# J1850_Tacho.net
KiCad netlist of a schematic drawn in Altium Designer
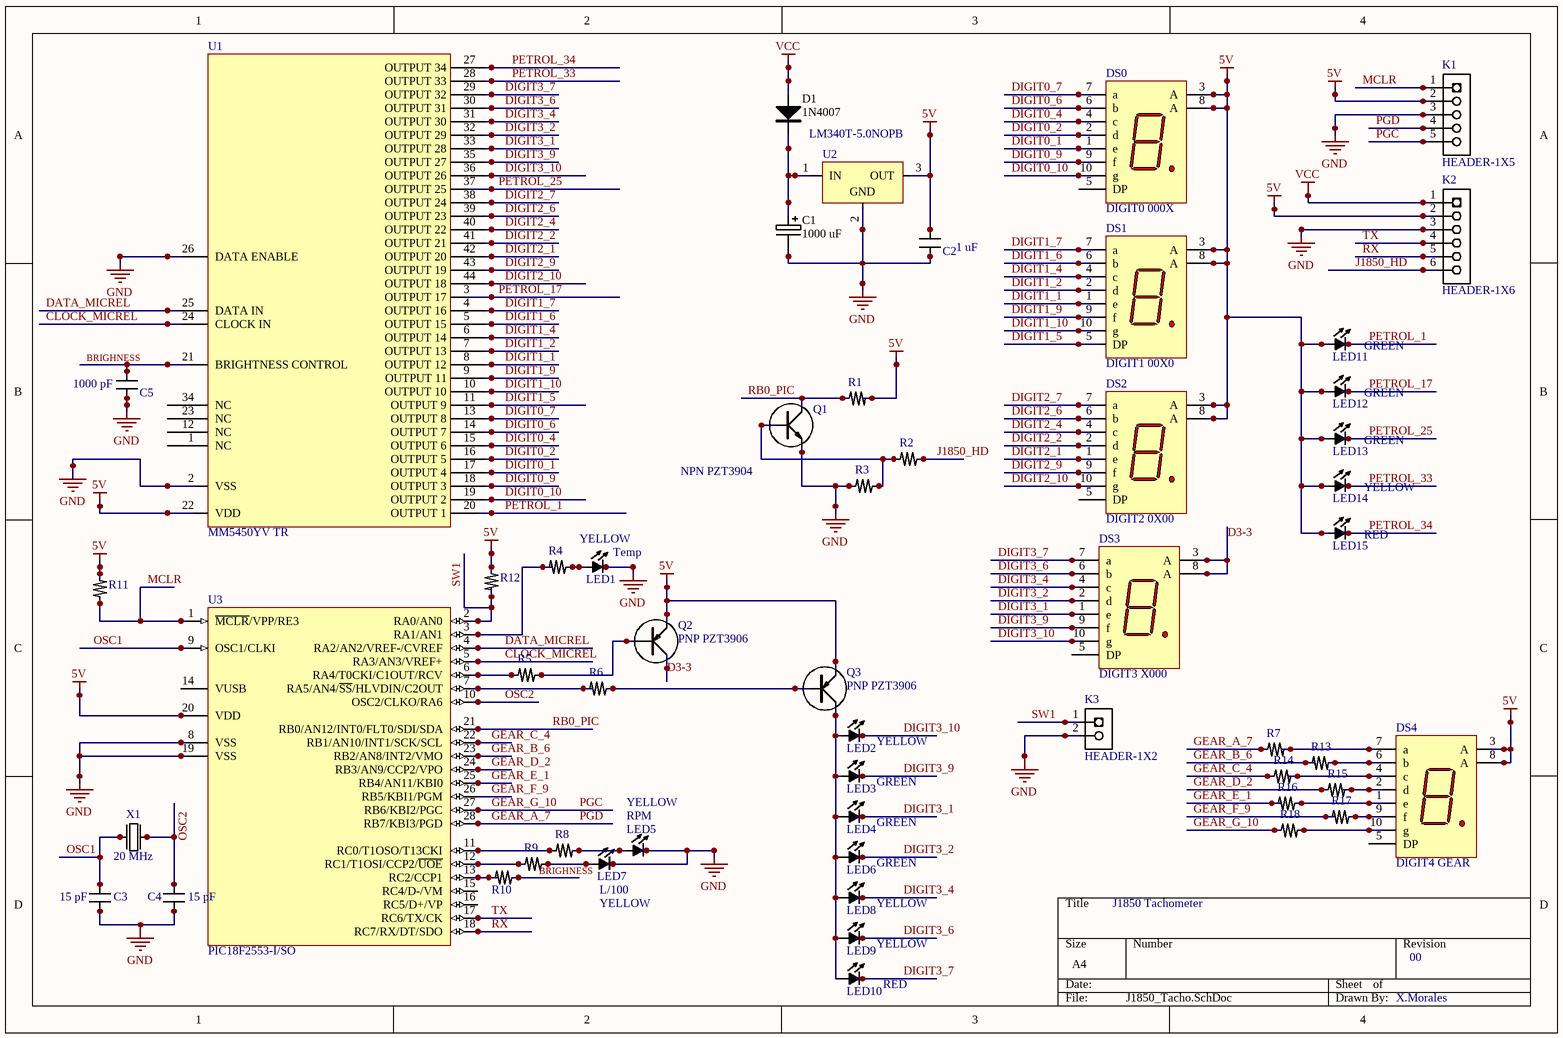
[diagram p0: J1850_Tacho.SchDoc]

(export (version "E")
  (design (tool "Eeschema 10.0.6"))
  (components
    (comp (ref "C1")
      (value "1000 uF")
      (footprint "AXIAL CAP")
      (description "AXIAL CAPACITOR")
      (libsource (lib "J1850_tacho") (part "AXIAL CAP"))
    )
    (comp (ref "C2")
      (value "1 uF")
      (footprint "C_0805")
      (description "Capacitor SMD 0805")
      (fields (field (name "PUBLISHER") "Altium Limited"))
      (libsource (lib "J1850_tacho") (part "Capacitor SMD 0805"))
    )
    (comp (ref "C3")
      (value "15 pF")
      (footprint "C_0805")
      (description "Capacitor SMD 0805")
      (fields (field (name "PUBLISHER") "Altium Limited"))
      (libsource (lib "J1850_tacho") (part "Capacitor SMD 0805"))
    )
    (comp (ref "C4")
      (value "15 pF")
      (footprint "C_0805")
      (description "Capacitor SMD 0805")
      (fields (field (name "PUBLISHER") "Altium Limited"))
      (libsource (lib "J1850_tacho") (part "Capacitor SMD 0805"))
    )
    (comp (ref "C5")
      (value "1000 pF")
      (footprint "C_0805")
      (description "Capacitor SMD 0805")
      (fields (field (name "PUBLISHER") "Altium Limited"))
      (libsource (lib "J1850_tacho") (part "Capacitor SMD 0805"))
    )
    (comp (ref "D1")
      (value "1N4007")
      (footprint "1N400X")
      (description "1N4001")
      (libsource (lib "J1850_tacho") (part "1N4001"))
    )
    (comp (ref "DS0")
      (value "SA56-51ZGWA")
      (footprint "H-10")
      (description "14.22 mm Low Current HER 7-Segment Display: CA, RH DP")
      (libsource (lib "J1850_tacho") (part "7Segment"))
    )
    (comp (ref "DS1")
      (value "SA56-51ZGWA")
      (footprint "H-10")
      (description "14.22 mm Low Current HER 7-Segment Display: CA, RH DP")
      (fields (field (name "PUBLISHER") "Altium Limited"))
      (libsource (lib "J1850_tacho") (part "HDSP-5551"))
    )
    (comp (ref "DS2")
      (value "SA56-51ZGWA")
      (footprint "H-10")
      (description "14.22 mm Low Current HER 7-Segment Display: CA, RH DP")
      (fields (field (name "PUBLISHER") "Altium Limited"))
      (libsource (lib "J1850_tacho") (part "HDSP-5551"))
    )
    (comp (ref "DS3")
      (value "SA56-51ZGWA")
      (footprint "H-10")
      (description "14.22 mm Low Current HER 7-Segment Display: CA, RH DP")
      (fields (field (name "PUBLISHER") "Altium Limited"))
      (libsource (lib "J1850_tacho") (part "HDSP-5551"))
    )
    (comp (ref "DS4")
      (value "SA56-51ZGWA")
      (footprint "H-10")
      (description "14.22 mm Low Current HER 7-Segment Display: CA, RH DP")
      (fields (field (name "PUBLISHER") "Altium Limited"))
      (libsource (lib "J1850_tacho") (part "HDSP-5551"))
    )
    (comp (ref "K1")
      (value "HEADER-1X5")
      (footprint "HEADER-1X5")
      (description "PINHEADER 1X5")
      (libsource (lib "J1850_tacho") (part "HEADER-1X5"))
    )
    (comp (ref "K2")
      (value "HEADER-1X6")
      (footprint "HEADER-1X6")
      (libsource (lib "J1850_tacho") (part "HEADER-1X6"))
    )
    (comp (ref "K3")
      (value "HEADER-1X2")
      (footprint "HEADER-1X2")
      (libsource (lib "J1850_tacho") (part "HEADER-1X2"))
    )
    (comp (ref "LED1")
      (value "YELLOW")
      (footprint "LED_0805")
      (description "LED SMD 0805")
      (libsource (lib "J1850_tacho") (part "LED SMD 0805"))
    )
    (comp (ref "LED2")
      (value "YELLOW")
      (footprint "LED_0805")
      (description "LED SMD 0805")
      (libsource (lib "J1850_tacho") (part "LED SMD 0805"))
    )
    (comp (ref "LED3")
      (value "GREEN")
      (footprint "LED_0805")
      (description "LED SMD 0805")
      (libsource (lib "J1850_tacho") (part "LED SMD 0805"))
    )
    (comp (ref "LED4")
      (value "GREEN")
      (footprint "LED_0805")
      (description "LED SMD 0805")
      (libsource (lib "J1850_tacho") (part "LED SMD 0805"))
    )
    (comp (ref "LED5")
      (value "YELLOW")
      (footprint "LED_0805")
      (description "LED SMD 0805")
      (libsource (lib "J1850_tacho") (part "LED SMD 0805"))
    )
    (comp (ref "LED6")
      (value "GREEN")
      (footprint "LED_0805")
      (description "LED SMD 0805")
      (libsource (lib "J1850_tacho") (part "LED SMD 0805"))
    )
    (comp (ref "LED7")
      (value "YELLOW")
      (footprint "LED_0805")
      (description "LED SMD 0805")
      (libsource (lib "J1850_tacho") (part "LED SMD 0805"))
    )
    (comp (ref "LED8")
      (value "YELLOW")
      (footprint "LED_0805")
      (description "LED SMD 0805")
      (libsource (lib "J1850_tacho") (part "LED SMD 0805"))
    )
    (comp (ref "LED9")
      (value "YELLOW")
      (footprint "LED_0805")
      (description "LED SMD 0805")
      (libsource (lib "J1850_tacho") (part "LED SMD 0805"))
    )
    (comp (ref "LED10")
      (value "RED")
      (footprint "LED_0805")
      (description "LED SMD 0805")
      (libsource (lib "J1850_tacho") (part "LED SMD 0805"))
    )
    (comp (ref "LED11")
      (value "GREEN")
      (footprint "LED_0805")
      (description "LED SMD 0805")
      (libsource (lib "J1850_tacho") (part "LED SMD 0805"))
    )
    (comp (ref "LED12")
      (value "GREEN")
      (footprint "LED_0805")
      (description "LED SMD 0805")
      (libsource (lib "J1850_tacho") (part "LED SMD 0805"))
    )
    (comp (ref "LED13")
      (value "GREEN")
      (footprint "LED_0805")
      (description "LED SMD 0805")
      (libsource (lib "J1850_tacho") (part "LED SMD 0805"))
    )
    (comp (ref "LED14")
      (value "YELLOW")
      (footprint "LED_0805")
      (description "LED SMD 0805")
      (libsource (lib "J1850_tacho") (part "LED SMD 0805"))
    )
    (comp (ref "LED15")
      (value "RED")
      (footprint "LED_0805")
      (description "LED SMD 0805")
      (libsource (lib "J1850_tacho") (part "LED SMD 0805"))
    )
    (comp (ref "Q1")
      (value "NPN PZT3904")
      (footprint "SOT223")
      (description "NPN TRANSISTOR")
      (libsource (lib "J1850_tacho") (part "NPN TRANSISTOR"))
    )
    (comp (ref "Q2")
      (value "PNP PZT3906")
      (footprint "SOT223")
      (description "PNP TRANSISTOR")
      (libsource (lib "J1850_tacho") (part "PNP TRANSISTOR"))
    )
    (comp (ref "Q3")
      (value "PNP PZT3906")
      (footprint "SOT223")
      (description "PNP TRANSISTOR")
      (libsource (lib "J1850_tacho") (part "PNP TRANSISTOR"))
    )
    (comp (ref "R1")
      (value "47 kOhm")
      (footprint "R_0805")
      (description "Resistor SMD 0805")
      (libsource (lib "J1850_tacho") (part "Resistor SMD 0805"))
    )
    (comp (ref "R2")
      (value "47 kOhm")
      (footprint "R_0805")
      (description "Resistor SMD 0805")
      (libsource (lib "J1850_tacho") (part "Resistor SMD 0805"))
    )
    (comp (ref "R3")
      (value "10 kOhm")
      (footprint "R_0805")
      (description "Resistor SMD 0805")
      (libsource (lib "J1850_tacho") (part "Resistor SMD 0805"))
    )
    (comp (ref "R4")
      (value "220 Ohm")
      (footprint "R_0805")
      (description "Resistor SMD 0805")
      (libsource (lib "J1850_tacho") (part "Resistor SMD 0805"))
    )
    (comp (ref "R5")
      (value "1 kOhm")
      (footprint "R_0805")
      (description "Resistor SMD 0805")
      (libsource (lib "J1850_tacho") (part "Resistor SMD 0805"))
    )
    (comp (ref "R6")
      (value "1 kOhm")
      (footprint "R_0805")
      (description "Resistor SMD 0805")
      (libsource (lib "J1850_tacho") (part "Resistor SMD 0805"))
    )
    (comp (ref "R7")
      (value "220 Ohm")
      (footprint "R_0805")
      (description "Resistor SMD 0805")
      (libsource (lib "J1850_tacho") (part "Resistor SMD 0805"))
    )
    (comp (ref "R8")
      (value "220 Ohm")
      (footprint "R_0805")
      (description "Resistor SMD 0805")
      (libsource (lib "J1850_tacho") (part "Resistor SMD 0805"))
    )
    (comp (ref "R9")
      (value "220 Ohm")
      (footprint "R_0805")
      (description "Resistor SMD 0805")
      (libsource (lib "J1850_tacho") (part "Resistor SMD 0805"))
    )
    (comp (ref "R10")
      (value "1200 Ohm")
      (footprint "R_0805")
      (description "Resistor SMD 0805")
      (libsource (lib "J1850_tacho") (part "Resistor SMD 0805"))
    )
    (comp (ref "R11")
      (value "10 kOhm")
      (footprint "R_0805")
      (description "Resistor SMD 0805")
      (libsource (lib "J1850_tacho") (part "Resistor SMD 0805"))
    )
    (comp (ref "R12")
      (value "10 kOhm")
      (footprint "R_0805")
      (description "Resistor SMD 0805")
      (libsource (lib "J1850_tacho") (part "Resistor SMD 0805"))
    )
    (comp (ref "R13")
      (value "220 Ohm")
      (footprint "R_0805")
      (description "Resistor SMD 0805")
      (libsource (lib "J1850_tacho") (part "Resistor SMD 0805"))
    )
    (comp (ref "R14")
      (value "220 Ohm")
      (footprint "R_0805")
      (description "Resistor SMD 0805")
      (libsource (lib "J1850_tacho") (part "Resistor SMD 0805"))
    )
    (comp (ref "R15")
      (value "220 Ohm")
      (footprint "R_0805")
      (description "Resistor SMD 0805")
      (libsource (lib "J1850_tacho") (part "Resistor SMD 0805"))
    )
    (comp (ref "R16")
      (value "220 Ohm")
      (footprint "R_0805")
      (description "Resistor SMD 0805")
      (libsource (lib "J1850_tacho") (part "Resistor SMD 0805"))
    )
    (comp (ref "R17")
      (value "220 Ohm")
      (footprint "R_0805")
      (description "Resistor SMD 0805")
      (libsource (lib "J1850_tacho") (part "Resistor SMD 0805"))
    )
    (comp (ref "R18")
      (value "220 Ohm")
      (footprint "R_0805")
      (description "Resistor SMD 0805")
      (libsource (lib "J1850_tacho") (part "Resistor SMD 0805"))
    )
    (comp (ref "U1")
      (value "MM5450YV TR")
      (footprint "PLCC-L44_M")
      (description "IC DRIVER DISPLAY LED 44PLCC")
      (libsource (lib "J1850_tacho") (part "MM5450YV TR"))
    )
    (comp (ref "U2")
      (value "LM340T-5.0NOPB")
      (footprint "TO-220-3")
      (description "IC REG LDO  5V 1A TO220-3")
      (fields
        (field (name "DIGIKEY PART NUMBER") "LM340T-5.0/NOPB-ND")
        (field (name "MANUFACTURER PART NUMBER") "LM340T-5.0/NOPB")
      )
      (libsource (lib "J1850_tacho") (part "LM340T-5.0NOPB"))
    )
    (comp (ref "U3")
      (value "PIC18F2553-I/SO")
      (footprint "SOIC-SO28_M")
      (fields (field (name "PUBLISHER") "Altium Limited"))
      (libsource (lib "J1850_tacho") (part "PIC18F2553-I/SO"))
    )
    (comp (ref "X1")
      (value "20 MHz")
      (footprint "XTAL - HC-49U")
      (libsource (lib "J1850_tacho") (part "XTAL"))
    )
  )
  (nets
    (net (code "1") (name "/BRIGHNESS") (class "Default")
      (node (ref "C5") (pin "2") (pinfunction "2_2") (pintype "passive"))
      (node (ref "R10") (pin "1") (pinfunction "1_1") (pintype "passive"))
      (node (ref "U1") (pin "21") (pinfunction "BRIGHTNESS_CONTROL_21") (pintype "passive"))
    )
    (net (code "2") (name "/CLOCK_MICREL") (class "Default")
      (node (ref "U1") (pin "24") (pinfunction "CLOCK_IN_24") (pintype "passive"))
      (node (ref "U3") (pin "5") (pinfunction "RA3/AN3/VREF+_5") (pintype "bidirectional"))
    )
    (net (code "3") (name "/D3-3") (class "Default")
      (node (ref "DS3") (pin "3") (pinfunction "A_3") (pintype "passive"))
      (node (ref "DS3") (pin "8") (pinfunction "A_8") (pintype "passive"))
      (node (ref "Q2") (pin "C") (pinfunction "C_C") (pintype "passive"))
    )
    (net (code "4") (name "/DATA_MICREL") (class "Default")
      (node (ref "U1") (pin "25") (pinfunction "DATA_IN_25") (pintype "passive"))
      (node (ref "U3") (pin "4") (pinfunction "RA2/AN2/VREF-/CVREF_4") (pintype "bidirectional"))
    )
    (net (code "5") (name "/DIGIT0_1") (class "Default")
      (node (ref "DS0") (pin "1") (pinfunction "e_1") (pintype "passive"))
      (node (ref "U1") (pin "17") (pinfunction "OUTPUT_4_17") (pintype "passive"))
    )
    (net (code "6") (name "/DIGIT0_2") (class "Default")
      (node (ref "DS0") (pin "2") (pinfunction "d_2") (pintype "passive"))
      (node (ref "U1") (pin "16") (pinfunction "OUTPUT_5_16") (pintype "passive"))
    )
    (net (code "7") (name "/DIGIT0_4") (class "Default")
      (node (ref "DS0") (pin "4") (pinfunction "c_4") (pintype "passive"))
      (node (ref "U1") (pin "15") (pinfunction "OUTPUT_6_15") (pintype "passive"))
    )
    (net (code "8") (name "/DIGIT0_6") (class "Default")
      (node (ref "DS0") (pin "6") (pinfunction "b_6") (pintype "passive"))
      (node (ref "U1") (pin "14") (pinfunction "OUTPUT_7_14") (pintype "passive"))
    )
    (net (code "9") (name "/DIGIT0_7") (class "Default")
      (node (ref "DS0") (pin "7") (pinfunction "a_7") (pintype "passive"))
      (node (ref "U1") (pin "13") (pinfunction "OUTPUT_8_13") (pintype "passive"))
    )
    (net (code "10") (name "/DIGIT0_9") (class "Default")
      (node (ref "DS0") (pin "9") (pinfunction "f_9") (pintype "passive"))
      (node (ref "U1") (pin "18") (pinfunction "OUTPUT_3_18") (pintype "passive"))
    )
    (net (code "11") (name "/DIGIT0_10") (class "Default")
      (node (ref "DS0") (pin "10") (pinfunction "g_10") (pintype "passive"))
      (node (ref "U1") (pin "19") (pinfunction "OUTPUT_2_19") (pintype "passive"))
    )
    (net (code "12") (name "/DIGIT1_1") (class "Default")
      (node (ref "DS1") (pin "1") (pinfunction "e_1") (pintype "passive"))
      (node (ref "U1") (pin "8") (pinfunction "OUTPUT_12_8") (pintype "passive"))
    )
    (net (code "13") (name "/DIGIT1_2") (class "Default")
      (node (ref "DS1") (pin "2") (pinfunction "d_2") (pintype "passive"))
      (node (ref "U1") (pin "7") (pinfunction "OUTPUT_13_7") (pintype "passive"))
    )
    (net (code "14") (name "/DIGIT1_4") (class "Default")
      (node (ref "DS1") (pin "4") (pinfunction "c_4") (pintype "passive"))
      (node (ref "U1") (pin "6") (pinfunction "OUTPUT_14_6") (pintype "passive"))
    )
    (net (code "15") (name "/DIGIT1_5") (class "Default")
      (node (ref "DS1") (pin "5") (pinfunction "DP_5") (pintype "passive"))
      (node (ref "U1") (pin "11") (pinfunction "OUTPUT_9_11") (pintype "passive"))
    )
    (net (code "16") (name "/DIGIT1_6") (class "Default")
      (node (ref "DS1") (pin "6") (pinfunction "b_6") (pintype "passive"))
      (node (ref "U1") (pin "5") (pinfunction "OUTPUT_15_5") (pintype "passive"))
    )
    (net (code "17") (name "/DIGIT1_7") (class "Default")
      (node (ref "DS1") (pin "7") (pinfunction "a_7") (pintype "passive"))
      (node (ref "U1") (pin "4") (pinfunction "OUTPUT_16_4") (pintype "passive"))
    )
    (net (code "18") (name "/DIGIT1_9") (class "Default")
      (node (ref "DS1") (pin "9") (pinfunction "f_9") (pintype "passive"))
      (node (ref "U1") (pin "9") (pinfunction "OUTPUT_11_9") (pintype "passive"))
    )
    (net (code "19") (name "/DIGIT1_10") (class "Default")
      (node (ref "DS1") (pin "10") (pinfunction "g_10") (pintype "passive"))
      (node (ref "U1") (pin "10") (pinfunction "OUTPUT_10_10") (pintype "passive"))
    )
    (net (code "20") (name "/DIGIT2_1") (class "Default")
      (node (ref "DS2") (pin "1") (pinfunction "e_1") (pintype "passive"))
      (node (ref "U1") (pin "42") (pinfunction "OUTPUT_20_42") (pintype "passive"))
    )
    (net (code "21") (name "/DIGIT2_2") (class "Default")
      (node (ref "DS2") (pin "2") (pinfunction "d_2") (pintype "passive"))
      (node (ref "U1") (pin "41") (pinfunction "OUTPUT_21_41") (pintype "passive"))
    )
    (net (code "22") (name "/DIGIT2_4") (class "Default")
      (node (ref "DS2") (pin "4") (pinfunction "c_4") (pintype "passive"))
      (node (ref "U1") (pin "40") (pinfunction "OUTPUT_22_40") (pintype "passive"))
    )
    (net (code "23") (name "/DIGIT2_6") (class "Default")
      (node (ref "DS2") (pin "6") (pinfunction "b_6") (pintype "passive"))
      (node (ref "U1") (pin "39") (pinfunction "OUTPUT_23_39") (pintype "passive"))
    )
    (net (code "24") (name "/DIGIT2_7") (class "Default")
      (node (ref "DS2") (pin "7") (pinfunction "a_7") (pintype "passive"))
      (node (ref "U1") (pin "38") (pinfunction "OUTPUT_24_38") (pintype "passive"))
    )
    (net (code "25") (name "/DIGIT2_9") (class "Default")
      (node (ref "DS2") (pin "9") (pinfunction "f_9") (pintype "passive"))
      (node (ref "U1") (pin "43") (pinfunction "OUTPUT_19_43") (pintype "passive"))
    )
    (net (code "26") (name "/DIGIT2_10") (class "Default")
      (node (ref "DS2") (pin "10") (pinfunction "g_10") (pintype "passive"))
      (node (ref "U1") (pin "44") (pinfunction "OUTPUT_18_44") (pintype "passive"))
    )
    (net (code "27") (name "/DIGIT3_1") (class "Default")
      (node (ref "DS3") (pin "1") (pinfunction "e_1") (pintype "passive"))
      (node (ref "LED4") (pin "1") (pintype "passive"))
      (node (ref "U1") (pin "33") (pinfunction "OUTPUT_28_33") (pintype "passive"))
    )
    (net (code "28") (name "/DIGIT3_2") (class "Default")
      (node (ref "DS3") (pin "2") (pinfunction "d_2") (pintype "passive"))
      (node (ref "LED6") (pin "1") (pintype "passive"))
      (node (ref "U1") (pin "32") (pinfunction "OUTPUT_29_32") (pintype "passive"))
    )
    (net (code "29") (name "/DIGIT3_4") (class "Default")
      (node (ref "DS3") (pin "4") (pinfunction "c_4") (pintype "passive"))
      (node (ref "LED8") (pin "1") (pintype "passive"))
      (node (ref "U1") (pin "31") (pinfunction "OUTPUT_30_31") (pintype "passive"))
    )
    (net (code "30") (name "/DIGIT3_6") (class "Default")
      (node (ref "DS3") (pin "6") (pinfunction "b_6") (pintype "passive"))
      (node (ref "LED9") (pin "1") (pintype "passive"))
      (node (ref "U1") (pin "30") (pinfunction "OUTPUT_31_30") (pintype "passive"))
    )
    (net (code "31") (name "/DIGIT3_7") (class "Default")
      (node (ref "DS3") (pin "7") (pinfunction "a_7") (pintype "passive"))
      (node (ref "LED10") (pin "1") (pintype "passive"))
      (node (ref "U1") (pin "29") (pinfunction "OUTPUT_32_29") (pintype "passive"))
    )
    (net (code "32") (name "/DIGIT3_9") (class "Default")
      (node (ref "DS3") (pin "9") (pinfunction "f_9") (pintype "passive"))
      (node (ref "LED3") (pin "1") (pintype "passive"))
      (node (ref "U1") (pin "35") (pinfunction "OUTPUT_27_35") (pintype "passive"))
    )
    (net (code "33") (name "/DIGIT3_10") (class "Default")
      (node (ref "DS3") (pin "10") (pinfunction "g_10") (pintype "passive"))
      (node (ref "LED2") (pin "1") (pintype "passive"))
      (node (ref "U1") (pin "36") (pinfunction "OUTPUT_26_36") (pintype "passive"))
    )
    (net (code "34") (name "/GEAR_A_7") (class "Default")
      (node (ref "K1") (pin "4") (pintype "passive"))
      (node (ref "R7") (pin "2") (pinfunction "2_2") (pintype "passive"))
      (node (ref "U3") (pin "28") (pinfunction "RB7/KBI3/PGD_28") (pintype "bidirectional"))
    )
    (net (code "35") (name "/GEAR_B_6") (class "Default")
      (node (ref "R13") (pin "2") (pinfunction "2_2") (pintype "passive"))
      (node (ref "U3") (pin "23") (pinfunction "RB2/AN8/INT2/VMO_23") (pintype "bidirectional"))
    )
    (net (code "36") (name "/GEAR_C_4") (class "Default")
      (node (ref "R14") (pin "2") (pinfunction "2_2") (pintype "passive"))
      (node (ref "U3") (pin "22") (pinfunction "RB1/AN10/INT1/SCK/SCL_22") (pintype "bidirectional"))
    )
    (net (code "37") (name "/GEAR_D_2") (class "Default")
      (node (ref "R15") (pin "2") (pinfunction "2_2") (pintype "passive"))
      (node (ref "U3") (pin "24") (pinfunction "RB3/AN9/CCP2/VPO_24") (pintype "bidirectional"))
    )
    (net (code "38") (name "/GEAR_E_1") (class "Default")
      (node (ref "R16") (pin "2") (pinfunction "2_2") (pintype "passive"))
      (node (ref "U3") (pin "25") (pinfunction "RB4/AN11/KBI0_25") (pintype "bidirectional"))
    )
    (net (code "39") (name "/GEAR_F_9") (class "Default")
      (node (ref "R17") (pin "2") (pinfunction "2_2") (pintype "passive"))
      (node (ref "U3") (pin "26") (pinfunction "RB5/KBI1/PGM_26") (pintype "bidirectional"))
    )
    (net (code "40") (name "/GEAR_G_10") (class "Default")
      (node (ref "K1") (pin "5") (pintype "passive"))
      (node (ref "R18") (pin "2") (pinfunction "2_2") (pintype "passive"))
      (node (ref "U3") (pin "27") (pinfunction "RB6/KBI2/PGC_27") (pintype "bidirectional"))
    )
    (net (code "41") (name "/J1850_HD") (class "Default")
      (node (ref "K2") (pin "6") (pintype "passive"))
      (node (ref "R2") (pin "1") (pinfunction "1_1") (pintype "passive"))
    )
    (net (code "42") (name "/MCLR") (class "Default")
      (node (ref "K1") (pin "1") (pintype "passive"))
      (node (ref "R11") (pin "1") (pinfunction "1_1") (pintype "passive"))
      (node (ref "U3") (pin "1") (pinfunction "~{MCLR}/VPP/RE3_1") (pintype "input"))
    )
    (net (code "43") (name "/OSC1") (class "Default")
      (node (ref "C3") (pin "2") (pinfunction "2_2") (pintype "passive"))
      (node (ref "U3") (pin "9") (pinfunction "OSC1/CLKI_9") (pintype "input"))
      (node (ref "X1") (pin "1") (pinfunction "1_1") (pintype "passive"))
    )
    (net (code "44") (name "/OSC2") (class "Default")
      (node (ref "C4") (pin "2") (pinfunction "2_2") (pintype "passive"))
      (node (ref "U3") (pin "10") (pinfunction "OSC2/CLKO/RA6_10") (pintype "bidirectional"))
      (node (ref "X1") (pin "2") (pinfunction "2_2") (pintype "passive"))
    )
    (net (code "45") (name "/PETROL_1") (class "Default")
      (node (ref "LED11") (pin "1") (pintype "passive"))
      (node (ref "U1") (pin "20") (pinfunction "OUTPUT_1_20") (pintype "passive"))
    )
    (net (code "46") (name "/PETROL_17") (class "Default")
      (node (ref "LED12") (pin "1") (pintype "passive"))
      (node (ref "U1") (pin "3") (pinfunction "OUTPUT_17_3") (pintype "passive"))
    )
    (net (code "47") (name "/PETROL_25") (class "Default")
      (node (ref "LED13") (pin "1") (pintype "passive"))
      (node (ref "U1") (pin "37") (pinfunction "OUTPUT_25_37") (pintype "passive"))
    )
    (net (code "48") (name "/PETROL_33") (class "Default")
      (node (ref "LED14") (pin "1") (pintype "passive"))
      (node (ref "U1") (pin "28") (pinfunction "OUTPUT_33_28") (pintype "passive"))
    )
    (net (code "49") (name "/PETROL_34") (class "Default")
      (node (ref "LED15") (pin "1") (pintype "passive"))
      (node (ref "U1") (pin "27") (pinfunction "OUTPUT_34_27") (pintype "passive"))
    )
    (net (code "50") (name "/RB0_PIC") (class "Default")
      (node (ref "Q1") (pin "C") (pinfunction "C_C") (pintype "passive"))
      (node (ref "R1") (pin "2") (pinfunction "2_2") (pintype "passive"))
      (node (ref "U3") (pin "21") (pinfunction "RB0/AN12/INT0/FLT0/SDI/SDA_21") (pintype "bidirectional"))
    )
    (net (code "51") (name "/RX") (class "Default")
      (node (ref "K2") (pin "5") (pintype "passive"))
      (node (ref "U3") (pin "18") (pinfunction "RC7/RX/DT/SDO_18") (pintype "bidirectional"))
    )
    (net (code "52") (name "/SW1") (class "Default")
      (node (ref "K3") (pin "1") (pintype "passive"))
      (node (ref "R12") (pin "1") (pinfunction "1_1") (pintype "passive"))
      (node (ref "U3") (pin "2") (pinfunction "RA0/AN0_2") (pintype "bidirectional"))
    )
    (net (code "53") (name "/TX") (class "Default")
      (node (ref "K2") (pin "4") (pintype "passive"))
      (node (ref "U3") (pin "17") (pinfunction "RC6/TX/CK_17") (pintype "bidirectional"))
    )
    (net (code "54") (name "5V") (class "Default")
      (node (ref "C2") (pin "2") (pinfunction "2_2") (pintype "passive"))
      (node (ref "DS0") (pin "3") (pinfunction "A_3") (pintype "passive"))
      (node (ref "DS0") (pin "8") (pinfunction "A_8") (pintype "passive"))
      (node (ref "DS1") (pin "3") (pinfunction "A_3") (pintype "passive"))
      (node (ref "DS1") (pin "8") (pinfunction "A_8") (pintype "passive"))
      (node (ref "DS2") (pin "3") (pinfunction "A_3") (pintype "passive"))
      (node (ref "DS2") (pin "8") (pinfunction "A_8") (pintype "passive"))
      (node (ref "DS4") (pin "3") (pinfunction "A_3") (pintype "passive"))
      (node (ref "DS4") (pin "8") (pinfunction "A_8") (pintype "passive"))
      (node (ref "K1") (pin "2") (pintype "passive"))
      (node (ref "K2") (pin "2") (pintype "passive"))
      (node (ref "LED11") (pin "2") (pintype "passive"))
      (node (ref "LED12") (pin "2") (pintype "passive"))
      (node (ref "LED13") (pin "2") (pintype "passive"))
      (node (ref "LED14") (pin "2") (pintype "passive"))
      (node (ref "LED15") (pin "2") (pintype "passive"))
      (node (ref "Q2") (pin "E") (pinfunction "E_E") (pintype "passive"))
      (node (ref "Q3") (pin "E") (pinfunction "E_E") (pintype "passive"))
      (node (ref "R1") (pin "1") (pinfunction "1_1") (pintype "passive"))
      (node (ref "R11") (pin "2") (pinfunction "2_2") (pintype "passive"))
      (node (ref "R12") (pin "2") (pinfunction "2_2") (pintype "passive"))
      (node (ref "U1") (pin "22") (pinfunction "VDD_22") (pintype "passive"))
      (node (ref "U2") (pin "3") (pinfunction "OUT_3") (pintype "power_in"))
      (node (ref "U3") (pin "20") (pinfunction "VDD_20") (pintype "power_in"))
    )
    (net (code "55") (name "GND") (class "Default")
      (node (ref "C1") (pin "2") (pinfunction "-_2") (pintype "passive"))
      (node (ref "C2") (pin "1") (pinfunction "1_1") (pintype "passive"))
      (node (ref "C3") (pin "1") (pinfunction "1_1") (pintype "passive"))
      (node (ref "C4") (pin "1") (pinfunction "1_1") (pintype "passive"))
      (node (ref "C5") (pin "1") (pinfunction "1_1") (pintype "passive"))
      (node (ref "K1") (pin "3") (pintype "passive"))
      (node (ref "K2") (pin "3") (pintype "passive"))
      (node (ref "K3") (pin "2") (pintype "passive"))
      (node (ref "LED1") (pin "1") (pintype "passive"))
      (node (ref "LED5") (pin "1") (pintype "passive"))
      (node (ref "LED7") (pin "1") (pintype "passive"))
      (node (ref "Q1") (pin "E") (pinfunction "E_E") (pintype "passive"))
      (node (ref "R3") (pin "2") (pinfunction "2_2") (pintype "passive"))
      (node (ref "U1") (pin "2") (pinfunction "VSS_2") (pintype "passive"))
      (node (ref "U1") (pin "26") (pinfunction "DATA_ENABLE_26") (pintype "passive"))
      (node (ref "U2") (pin "2") (pinfunction "GND_2") (pintype "power_in"))
      (node (ref "U3") (pin "19") (pinfunction "VSS_19") (pintype "power_in"))
      (node (ref "U3") (pin "8") (pinfunction "VSS_8") (pintype "power_in"))
    )
    (net (code "56") (name "Net-(C1-+)") (class "Default")
      (node (ref "C1") (pin "1") (pinfunction "+_1") (pintype "passive"))
      (node (ref "D1") (pin "K") (pinfunction "K_K") (pintype "passive"))
      (node (ref "U2") (pin "1") (pinfunction "IN_1") (pintype "power_in"))
    )
    (net (code "57") (name "Net-(DS4-a)") (class "Default")
      (node (ref "DS4") (pin "7") (pinfunction "a_7") (pintype "passive"))
      (node (ref "R7") (pin "1") (pinfunction "1_1") (pintype "passive"))
    )
    (net (code "58") (name "Net-(DS4-b)") (class "Default")
      (node (ref "DS4") (pin "6") (pinfunction "b_6") (pintype "passive"))
      (node (ref "R13") (pin "1") (pinfunction "1_1") (pintype "passive"))
    )
    (net (code "59") (name "Net-(DS4-c)") (class "Default")
      (node (ref "DS4") (pin "4") (pinfunction "c_4") (pintype "passive"))
      (node (ref "R14") (pin "1") (pinfunction "1_1") (pintype "passive"))
    )
    (net (code "60") (name "Net-(DS4-d)") (class "Default")
      (node (ref "DS4") (pin "2") (pinfunction "d_2") (pintype "passive"))
      (node (ref "R15") (pin "1") (pinfunction "1_1") (pintype "passive"))
    )
    (net (code "61") (name "Net-(DS4-e)") (class "Default")
      (node (ref "DS4") (pin "1") (pinfunction "e_1") (pintype "passive"))
      (node (ref "R16") (pin "1") (pinfunction "1_1") (pintype "passive"))
    )
    (net (code "62") (name "Net-(DS4-f)") (class "Default")
      (node (ref "DS4") (pin "9") (pinfunction "f_9") (pintype "passive"))
      (node (ref "R17") (pin "1") (pinfunction "1_1") (pintype "passive"))
    )
    (net (code "63") (name "Net-(DS4-g)") (class "Default")
      (node (ref "DS4") (pin "10") (pinfunction "g_10") (pintype "passive"))
      (node (ref "R18") (pin "1") (pinfunction "1_1") (pintype "passive"))
    )
    (net (code "64") (name "Net-(LED1-Pad2)") (class "Default")
      (node (ref "LED1") (pin "2") (pintype "passive"))
      (node (ref "R4") (pin "1") (pinfunction "1_1") (pintype "passive"))
    )
    (net (code "65") (name "Net-(LED5-Pad2)") (class "Default")
      (node (ref "LED5") (pin "2") (pintype "passive"))
      (node (ref "R8") (pin "1") (pinfunction "1_1") (pintype "passive"))
    )
    (net (code "66") (name "Net-(LED7-Pad2)") (class "Default")
      (node (ref "LED7") (pin "2") (pintype "passive"))
      (node (ref "R9") (pin "1") (pinfunction "1_1") (pintype "passive"))
    )
    (net (code "67") (name "Net-(LED10-Pad2)") (class "Default")
      (node (ref "LED10") (pin "2") (pintype "passive"))
      (node (ref "LED2") (pin "2") (pintype "passive"))
      (node (ref "LED3") (pin "2") (pintype "passive"))
      (node (ref "LED4") (pin "2") (pintype "passive"))
      (node (ref "LED6") (pin "2") (pintype "passive"))
      (node (ref "LED8") (pin "2") (pintype "passive"))
      (node (ref "LED9") (pin "2") (pintype "passive"))
      (node (ref "Q3") (pin "C") (pinfunction "C_C") (pintype "passive"))
    )
    (net (code "68") (name "Net-(Q1-PadB)") (class "Default")
      (node (ref "Q1") (pin "B") (pinfunction "B_B") (pintype "passive"))
      (node (ref "R2") (pin "2") (pinfunction "2_2") (pintype "passive"))
      (node (ref "R3") (pin "1") (pinfunction "1_1") (pintype "passive"))
    )
    (net (code "69") (name "Net-(Q2-PadB)") (class "Default")
      (node (ref "Q2") (pin "B") (pinfunction "B_B") (pintype "passive"))
      (node (ref "R5") (pin "1") (pinfunction "1_1") (pintype "passive"))
    )
    (net (code "70") (name "Net-(Q3-PadB)") (class "Default")
      (node (ref "Q3") (pin "B") (pinfunction "B_B") (pintype "passive"))
      (node (ref "R6") (pin "1") (pinfunction "1_1") (pintype "passive"))
    )
    (net (code "71") (name "Net-(U3-RA1{slash}AN1)") (class "Default")
      (node (ref "R4") (pin "2") (pinfunction "2_2") (pintype "passive"))
      (node (ref "U3") (pin "3") (pinfunction "RA1/AN1_3") (pintype "bidirectional"))
    )
    (net (code "72") (name "Net-(U3-RA4{slash}T0CKI{slash}C1OUT{slash}RCV)") (class "Default")
      (node (ref "R5") (pin "2") (pinfunction "2_2") (pintype "passive"))
      (node (ref "U3") (pin "6") (pinfunction "RA4/T0CKI/C1OUT/RCV_6") (pintype "bidirectional"))
    )
    (net (code "73") (name "Net-(U3-RA5{slash}AN4{slash}~{SS}{slash}HLVDIN{slash}C2OUT)") (class "Default")
      (node (ref "R6") (pin "2") (pinfunction "2_2") (pintype "passive"))
      (node (ref "U3") (pin "7") (pinfunction "RA5/AN4/~{SS}/HLVDIN/C2OUT_7") (pintype "bidirectional"))
    )
    (net (code "74") (name "Net-(U3-RC0{slash}T1OSO{slash}T13CKI)") (class "Default")
      (node (ref "R8") (pin "2") (pinfunction "2_2") (pintype "passive"))
      (node (ref "U3") (pin "11") (pinfunction "RC0/T1OSO/T13CKI_11") (pintype "bidirectional"))
    )
    (net (code "75") (name "Net-(U3-RC1{slash}T1OSI{slash}CCP2{slash}~{UOE})") (class "Default")
      (node (ref "R9") (pin "2") (pinfunction "2_2") (pintype "passive"))
      (node (ref "U3") (pin "12") (pinfunction "RC1/T1OSI/CCP2/~{UOE}_12") (pintype "bidirectional"))
    )
    (net (code "76") (name "Net-(U3-RC2{slash}CCP1)") (class "Default")
      (node (ref "R10") (pin "2") (pinfunction "2_2") (pintype "passive"))
      (node (ref "U3") (pin "13") (pinfunction "RC2/CCP1_13") (pintype "bidirectional"))
    )
    (net (code "77") (name "VCC") (class "Default")
      (node (ref "D1") (pin "A") (pinfunction "A_A") (pintype "passive"))
      (node (ref "K2") (pin "1") (pintype "passive"))
    )
    (net (code "78") (name "unconnected-(DS0-DP-Pad5)") (class "Default")
      (node (ref "DS0") (pin "5") (pinfunction "DP_5") (pintype "passive"))
    )
    (net (code "79") (name "unconnected-(DS2-DP-Pad5)") (class "Default")
      (node (ref "DS2") (pin "5") (pinfunction "DP_5") (pintype "passive"))
    )
    (net (code "80") (name "unconnected-(DS3-DP-Pad5)") (class "Default")
      (node (ref "DS3") (pin "5") (pinfunction "DP_5") (pintype "passive"))
    )
    (net (code "81") (name "unconnected-(DS4-DP-Pad5)") (class "Default")
      (node (ref "DS4") (pin "5") (pinfunction "DP_5") (pintype "passive"))
    )
    (net (code "82") (name "unconnected-(U1-NC-Pad1)") (class "Default")
      (node (ref "U1") (pin "1") (pinfunction "NC_1") (pintype "passive"))
    )
    (net (code "83") (name "unconnected-(U1-NC-Pad12)") (class "Default")
      (node (ref "U1") (pin "12") (pinfunction "NC_12") (pintype "passive"))
    )
    (net (code "84") (name "unconnected-(U1-NC-Pad23)") (class "Default")
      (node (ref "U1") (pin "23") (pinfunction "NC_23") (pintype "passive"))
    )
    (net (code "85") (name "unconnected-(U1-NC-Pad34)") (class "Default")
      (node (ref "U1") (pin "34") (pinfunction "NC_34") (pintype "passive"))
    )
    (net (code "86") (name "unconnected-(U3-RC4{slash}D-{slash}VM-Pad15)") (class "Default")
      (node (ref "U3") (pin "15") (pinfunction "RC4/D-/VM_15") (pintype "bidirectional"))
    )
    (net (code "87") (name "unconnected-(U3-RC5{slash}D+{slash}VP-Pad16)") (class "Default")
      (node (ref "U3") (pin "16") (pinfunction "RC5/D+/VP_16") (pintype "bidirectional"))
    )
    (net (code "88") (name "unconnected-(U3-VUSB-Pad14)") (class "Default")
      (node (ref "U3") (pin "14") (pinfunction "VUSB_14") (pintype "power_in"))
    )
  )
)
